# mixer.net
KiCad netlist of a schematic drawn in Altium Designer
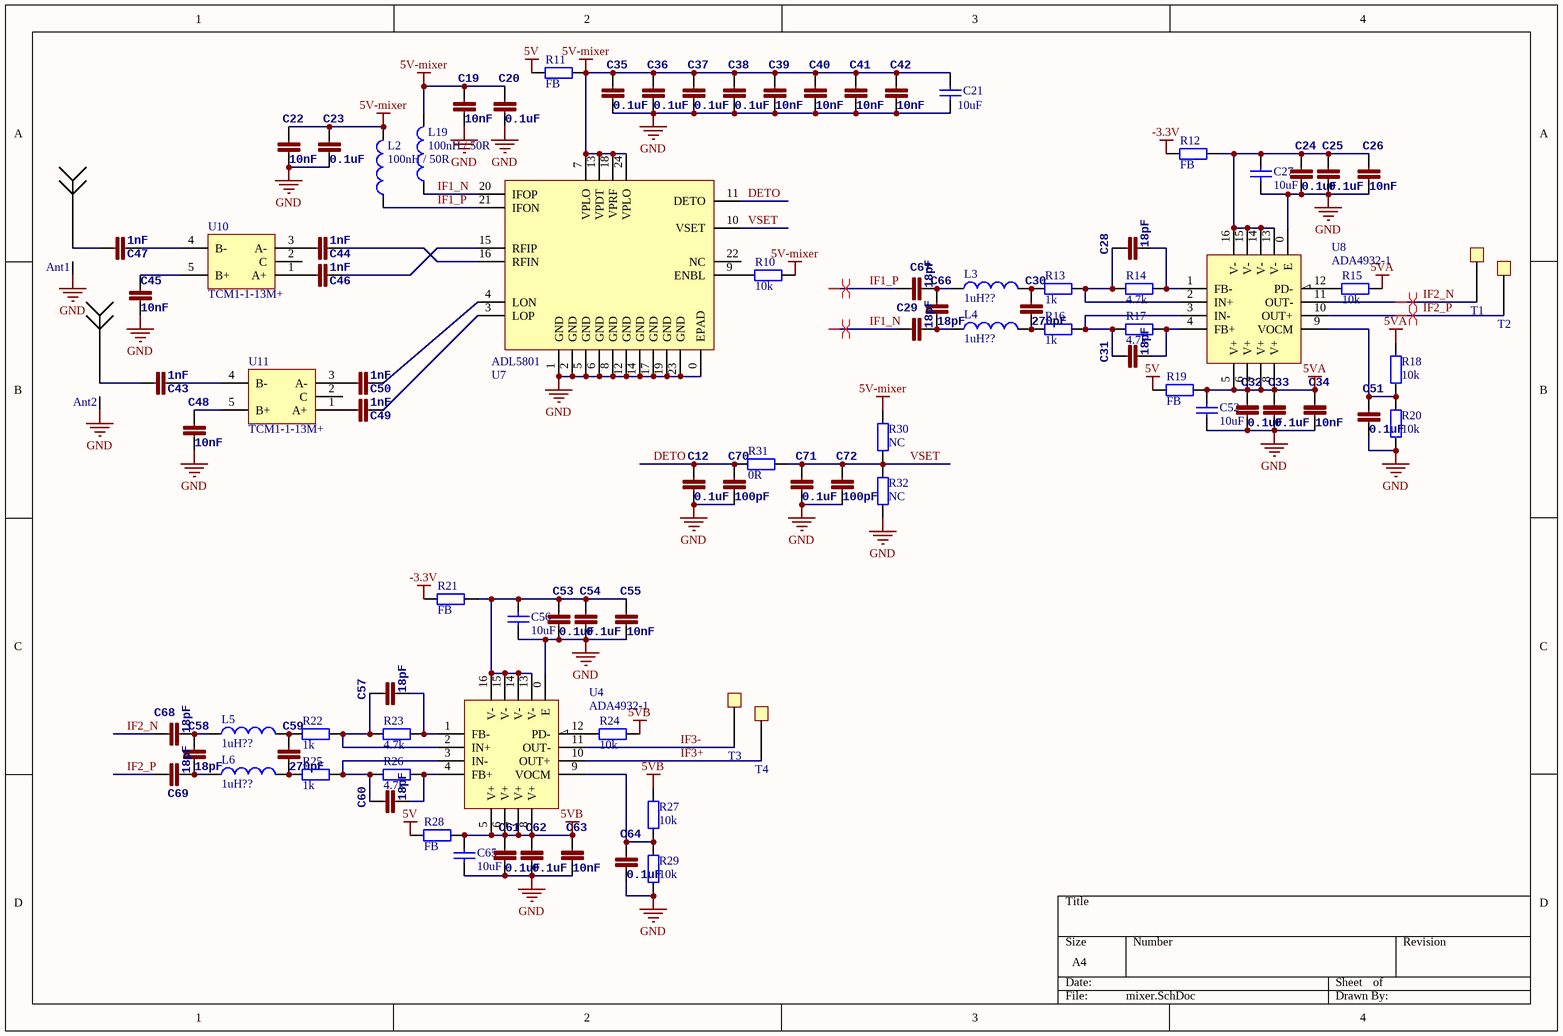
[diagram p0: mixer.SchDoc]

(export (version "E")
  (design (tool "Eeschema 10.0.6"))
  (components
    (comp (ref "Ant1") (value "Antenna") (footprint "SMA-2") (libsource (lib "F4SDR") (part "Antenna")))
    (comp (ref "Ant2") (value "Antenna") (footprint "SMA-2") (libsource (lib "F4SDR") (part "Antenna")))
    (comp (ref "C12")
      (value "0.1uF")
      (footprint "0402")
      (description "<b>Capacitor</b>\nStandard 0603 ceramic capacitor, and 0.1\" leaded capacitor.")
      (fields (field (name "PARTNO") "CC0402ZRY5V7BB104"))
      (libsource (lib "") (part "CAP0402-CAP_1"))
    )
    (comp (ref "C19")
      (value "10nF")
      (footprint "0402")
      (description "<b>Capacitor</b>\nStandard 0603 ceramic capacitor, and 0.1\" leaded capacitor.")
      (fields (field (name "PARTNO") "CC0402ZRY5V7BB104"))
      (libsource (lib "") (part "CAP0402-CAP_1"))
    )
    (comp (ref "C20")
      (value "0.1uF")
      (footprint "0402")
      (description "<b>Capacitor</b>\nStandard 0603 ceramic capacitor, and 0.1\" leaded capacitor.")
      (fields (field (name "PARTNO") "CC0402ZRY5V7BB104"))
      (libsource (lib "") (part "CAP0402-CAP_1"))
    )
    (comp (ref "C21")
      (value "10uF")
      (footprint "0805")
      (description "Capacitor")
      (fields (field (name "PUBLISHER") "Altium Limited"))
      (libsource (lib "RTC6705") (part "Cap"))
    )
    (comp (ref "C22")
      (value "10nF")
      (footprint "0402")
      (description "<b>Capacitor</b>\nStandard 0603 ceramic capacitor, and 0.1\" leaded capacitor.")
      (fields (field (name "PARTNO") "CC0402ZRY5V7BB104"))
      (libsource (lib "") (part "CAP0402-CAP_1"))
    )
    (comp (ref "C23")
      (value "0.1uF")
      (footprint "0402")
      (description "<b>Capacitor</b>\nStandard 0603 ceramic capacitor, and 0.1\" leaded capacitor.")
      (fields (field (name "PARTNO") "CC0402ZRY5V7BB104"))
      (libsource (lib "") (part "CAP0402-CAP_1"))
    )
    (comp (ref "C24")
      (value "0.1uF")
      (footprint "0402")
      (description "<b>Capacitor</b>\nStandard 0603 ceramic capacitor, and 0.1\" leaded capacitor.")
      (fields (field (name "PARTNO") "CC0402ZRY5V7BB104"))
      (libsource (lib "") (part "CAP0402-CAP_1"))
    )
    (comp (ref "C25")
      (value "0.1uF")
      (footprint "0402")
      (description "<b>Capacitor</b>\nStandard 0603 ceramic capacitor, and 0.1\" leaded capacitor.")
      (fields (field (name "PARTNO") "CC0402ZRY5V7BB104"))
      (libsource (lib "") (part "CAP0402-CAP_1"))
    )
    (comp (ref "C26")
      (value "10nF")
      (footprint "0402")
      (description "<b>Capacitor</b>\nStandard 0603 ceramic capacitor, and 0.1\" leaded capacitor.")
      (fields (field (name "PARTNO") "CC0402ZRY5V7BB104"))
      (libsource (lib "") (part "CAP0402-CAP_1"))
    )
    (comp (ref "C27")
      (value "10uF")
      (footprint "0805")
      (description "Capacitor")
      (fields (field (name "PUBLISHER") "Altium Limited"))
      (libsource (lib "RTC6705") (part "Cap"))
    )
    (comp (ref "C28")
      (value "18pF")
      (footprint "0402")
      (description "<b>Capacitor</b>\nStandard 0603 ceramic capacitor, and 0.1\" leaded capacitor.")
      (fields (field (name "PARTNO") "CC0402ZRY5V7BB104"))
      (libsource (lib "") (part "CAP0402-CAP_2"))
    )
    (comp (ref "C29")
      (value "18pF")
      (footprint "0402")
      (description "<b>Capacitor</b>\nStandard 0603 ceramic capacitor, and 0.1\" leaded capacitor.")
      (fields (field (name "PARTNO") "CC0402ZRY5V7BB104"))
      (libsource (lib "") (part "CAP0402-CAP_2"))
    )
    (comp (ref "C30")
      (value "270pF")
      (footprint "0402")
      (description "<b>Capacitor</b>\nStandard 0603 ceramic capacitor, and 0.1\" leaded capacitor.")
      (fields (field (name "PARTNO") "CC0402ZRY5V7BB104"))
      (libsource (lib "") (part "CAP0402-CAP_1"))
    )
    (comp (ref "C31")
      (value "18pF")
      (footprint "0402")
      (description "<b>Capacitor</b>\nStandard 0603 ceramic capacitor, and 0.1\" leaded capacitor.")
      (fields (field (name "PARTNO") "CC0402ZRY5V7BB104"))
      (libsource (lib "") (part "CAP0402-CAP_2"))
    )
    (comp (ref "C32")
      (value "0.1uF")
      (footprint "0402")
      (description "<b>Capacitor</b>\nStandard 0603 ceramic capacitor, and 0.1\" leaded capacitor.")
      (fields (field (name "PARTNO") "CC0402ZRY5V7BB104"))
      (libsource (lib "") (part "CAP0402-CAP_1"))
    )
    (comp (ref "C33")
      (value "0.1uF")
      (footprint "0402")
      (description "<b>Capacitor</b>\nStandard 0603 ceramic capacitor, and 0.1\" leaded capacitor.")
      (fields (field (name "PARTNO") "CC0402ZRY5V7BB104"))
      (libsource (lib "") (part "CAP0402-CAP_1"))
    )
    (comp (ref "C34")
      (value "10nF")
      (footprint "0402")
      (description "<b>Capacitor</b>\nStandard 0603 ceramic capacitor, and 0.1\" leaded capacitor.")
      (fields (field (name "PARTNO") "CC0402ZRY5V7BB104"))
      (libsource (lib "") (part "CAP0402-CAP_1"))
    )
    (comp (ref "C35")
      (value "0.1uF")
      (footprint "0402")
      (description "<b>Capacitor</b>\nStandard 0603 ceramic capacitor, and 0.1\" leaded capacitor.")
      (fields (field (name "PARTNO") "CC0402ZRY5V7BB104"))
      (libsource (lib "") (part "CAP0402-CAP_1"))
    )
    (comp (ref "C36")
      (value "0.1uF")
      (footprint "0402")
      (description "<b>Capacitor</b>\nStandard 0603 ceramic capacitor, and 0.1\" leaded capacitor.")
      (fields (field (name "PARTNO") "CC0402ZRY5V7BB104"))
      (libsource (lib "") (part "CAP0402-CAP_1"))
    )
    (comp (ref "C37")
      (value "0.1uF")
      (footprint "0402")
      (description "<b>Capacitor</b>\nStandard 0603 ceramic capacitor, and 0.1\" leaded capacitor.")
      (fields (field (name "PARTNO") "CC0402ZRY5V7BB104"))
      (libsource (lib "") (part "CAP0402-CAP_1"))
    )
    (comp (ref "C38")
      (value "0.1uF")
      (footprint "0402")
      (description "<b>Capacitor</b>\nStandard 0603 ceramic capacitor, and 0.1\" leaded capacitor.")
      (fields (field (name "PARTNO") "CC0402ZRY5V7BB104"))
      (libsource (lib "") (part "CAP0402-CAP_1"))
    )
    (comp (ref "C39")
      (value "10nF")
      (footprint "0402")
      (description "<b>Capacitor</b>\nStandard 0603 ceramic capacitor, and 0.1\" leaded capacitor.")
      (fields (field (name "PARTNO") "CC0402ZRY5V7BB104"))
      (libsource (lib "") (part "CAP0402-CAP_1"))
    )
    (comp (ref "C40")
      (value "10nF")
      (footprint "0402")
      (description "<b>Capacitor</b>\nStandard 0603 ceramic capacitor, and 0.1\" leaded capacitor.")
      (fields (field (name "PARTNO") "CC0402ZRY5V7BB104"))
      (libsource (lib "") (part "CAP0402-CAP_1"))
    )
    (comp (ref "C41")
      (value "10nF")
      (footprint "0402")
      (description "<b>Capacitor</b>\nStandard 0603 ceramic capacitor, and 0.1\" leaded capacitor.")
      (fields (field (name "PARTNO") "CC0402ZRY5V7BB104"))
      (libsource (lib "") (part "CAP0402-CAP_1"))
    )
    (comp (ref "C42")
      (value "10nF")
      (footprint "0402")
      (description "<b>Capacitor</b>\nStandard 0603 ceramic capacitor, and 0.1\" leaded capacitor.")
      (fields (field (name "PARTNO") "CC0402ZRY5V7BB104"))
      (libsource (lib "") (part "CAP0402-CAP_1"))
    )
    (comp (ref "C43")
      (value "1nF")
      (footprint "0402")
      (description "<b>Capacitor</b>\nStandard 0603 ceramic capacitor, and 0.1\" leaded capacitor.")
      (fields (field (name "PARTNO") "CC0402ZRY5V7BB104"))
      (libsource (lib "*") (part "CAP0402-CAP"))
    )
    (comp (ref "C44")
      (value "1nF")
      (footprint "0402")
      (description "<b>Capacitor</b>\nStandard 0603 ceramic capacitor, and 0.1\" leaded capacitor.")
      (fields (field (name "PARTNO") "CC0402ZRY5V7BB104"))
      (libsource (lib "*") (part "CAP0402-CAP"))
    )
    (comp (ref "C45")
      (value "10nF")
      (footprint "0402")
      (description "<b>Capacitor</b>\nStandard 0603 ceramic capacitor, and 0.1\" leaded capacitor.")
      (fields (field (name "PARTNO") "CC0402ZRY5V7BB104"))
      (libsource (lib "") (part "CAP0402-CAP_1"))
    )
    (comp (ref "C46")
      (value "1nF")
      (footprint "0402")
      (description "<b>Capacitor</b>\nStandard 0603 ceramic capacitor, and 0.1\" leaded capacitor.")
      (fields (field (name "PARTNO") "CC0402ZRY5V7BB104"))
      (libsource (lib "*") (part "CAP0402-CAP"))
    )
    (comp (ref "C47")
      (value "1nF")
      (footprint "0402")
      (description "<b>Capacitor</b>\nStandard 0603 ceramic capacitor, and 0.1\" leaded capacitor.")
      (fields (field (name "PARTNO") "CC0402ZRY5V7BB104"))
      (libsource (lib "*") (part "CAP0402-CAP"))
    )
    (comp (ref "C48")
      (value "10nF")
      (footprint "0402")
      (description "<b>Capacitor</b>\nStandard 0603 ceramic capacitor, and 0.1\" leaded capacitor.")
      (fields (field (name "PARTNO") "CC0402ZRY5V7BB104"))
      (libsource (lib "") (part "CAP0402-CAP_1"))
    )
    (comp (ref "C49")
      (value "1nF")
      (footprint "0402")
      (description "<b>Capacitor</b>\nStandard 0603 ceramic capacitor, and 0.1\" leaded capacitor.")
      (fields (field (name "PARTNO") "CC0402ZRY5V7BB104"))
      (libsource (lib "*") (part "CAP0402-CAP"))
    )
    (comp (ref "C50")
      (value "1nF")
      (footprint "0402")
      (description "<b>Capacitor</b>\nStandard 0603 ceramic capacitor, and 0.1\" leaded capacitor.")
      (fields (field (name "PARTNO") "CC0402ZRY5V7BB104"))
      (libsource (lib "*") (part "CAP0402-CAP"))
    )
    (comp (ref "C51")
      (value "0.1uF")
      (footprint "0402")
      (description "<b>Capacitor</b>\nStandard 0603 ceramic capacitor, and 0.1\" leaded capacitor.")
      (fields (field (name "PARTNO") "CC0402ZRY5V7BB104"))
      (libsource (lib "") (part "CAP0402-CAP_1"))
    )
    (comp (ref "C52")
      (value "10uF")
      (footprint "0805")
      (description "Capacitor")
      (fields (field (name "PUBLISHER") "Altium Limited"))
      (libsource (lib "RTC6705") (part "Cap"))
    )
    (comp (ref "C53")
      (value "0.1uF")
      (footprint "0402")
      (description "<b>Capacitor</b>\nStandard 0603 ceramic capacitor, and 0.1\" leaded capacitor.")
      (fields (field (name "PARTNO") "CC0402ZRY5V7BB104"))
      (libsource (lib "") (part "CAP0402-CAP_1"))
    )
    (comp (ref "C54")
      (value "0.1uF")
      (footprint "0402")
      (description "<b>Capacitor</b>\nStandard 0603 ceramic capacitor, and 0.1\" leaded capacitor.")
      (fields (field (name "PARTNO") "CC0402ZRY5V7BB104"))
      (libsource (lib "") (part "CAP0402-CAP_1"))
    )
    (comp (ref "C55")
      (value "10nF")
      (footprint "0402")
      (description "<b>Capacitor</b>\nStandard 0603 ceramic capacitor, and 0.1\" leaded capacitor.")
      (fields (field (name "PARTNO") "CC0402ZRY5V7BB104"))
      (libsource (lib "") (part "CAP0402-CAP_1"))
    )
    (comp (ref "C56")
      (value "10uF")
      (footprint "0805")
      (description "Capacitor")
      (fields (field (name "PUBLISHER") "Altium Limited"))
      (libsource (lib "RTC6705") (part "Cap"))
    )
    (comp (ref "C57")
      (value "18pF")
      (footprint "0402")
      (description "<b>Capacitor</b>\nStandard 0603 ceramic capacitor, and 0.1\" leaded capacitor.")
      (fields (field (name "PARTNO") "CC0402ZRY5V7BB104"))
      (libsource (lib "") (part "CAP0402-CAP_2"))
    )
    (comp (ref "C58")
      (value "18pF")
      (footprint "0402")
      (description "<b>Capacitor</b>\nStandard 0603 ceramic capacitor, and 0.1\" leaded capacitor.")
      (fields (field (name "PARTNO") "CC0402ZRY5V7BB104"))
      (libsource (lib "") (part "CAP0402-CAP_1"))
    )
    (comp (ref "C59")
      (value "270pF")
      (footprint "0402")
      (description "<b>Capacitor</b>\nStandard 0603 ceramic capacitor, and 0.1\" leaded capacitor.")
      (fields (field (name "PARTNO") "CC0402ZRY5V7BB104"))
      (libsource (lib "") (part "CAP0402-CAP_1"))
    )
    (comp (ref "C60")
      (value "18pF")
      (footprint "0402")
      (description "<b>Capacitor</b>\nStandard 0603 ceramic capacitor, and 0.1\" leaded capacitor.")
      (fields (field (name "PARTNO") "CC0402ZRY5V7BB104"))
      (libsource (lib "") (part "CAP0402-CAP_2"))
    )
    (comp (ref "C61")
      (value "0.1uF")
      (footprint "0402")
      (description "<b>Capacitor</b>\nStandard 0603 ceramic capacitor, and 0.1\" leaded capacitor.")
      (fields (field (name "PARTNO") "CC0402ZRY5V7BB104"))
      (libsource (lib "") (part "CAP0402-CAP_1"))
    )
    (comp (ref "C62")
      (value "0.1uF")
      (footprint "0402")
      (description "<b>Capacitor</b>\nStandard 0603 ceramic capacitor, and 0.1\" leaded capacitor.")
      (fields (field (name "PARTNO") "CC0402ZRY5V7BB104"))
      (libsource (lib "") (part "CAP0402-CAP_1"))
    )
    (comp (ref "C63")
      (value "10nF")
      (footprint "0402")
      (description "<b>Capacitor</b>\nStandard 0603 ceramic capacitor, and 0.1\" leaded capacitor.")
      (fields (field (name "PARTNO") "CC0402ZRY5V7BB104"))
      (libsource (lib "") (part "CAP0402-CAP_1"))
    )
    (comp (ref "C64")
      (value "0.1uF")
      (footprint "0402")
      (description "<b>Capacitor</b>\nStandard 0603 ceramic capacitor, and 0.1\" leaded capacitor.")
      (fields (field (name "PARTNO") "CC0402ZRY5V7BB104"))
      (libsource (lib "") (part "CAP0402-CAP_1"))
    )
    (comp (ref "C65")
      (value "10uF")
      (footprint "0805")
      (description "Capacitor")
      (fields (field (name "PUBLISHER") "Altium Limited"))
      (libsource (lib "RTC6705") (part "Cap"))
    )
    (comp (ref "C66")
      (value "18pF")
      (footprint "0402")
      (description "<b>Capacitor</b>\nStandard 0603 ceramic capacitor, and 0.1\" leaded capacitor.")
      (fields (field (name "PARTNO") "CC0402ZRY5V7BB104"))
      (libsource (lib "") (part "CAP0402-CAP_1"))
    )
    (comp (ref "C67")
      (value "18pF")
      (footprint "0402")
      (description "<b>Capacitor</b>\nStandard 0603 ceramic capacitor, and 0.1\" leaded capacitor.")
      (fields (field (name "PARTNO") "CC0402ZRY5V7BB104"))
      (libsource (lib "") (part "CAP0402-CAP_2"))
    )
    (comp (ref "C68")
      (value "18pF")
      (footprint "0402")
      (description "<b>Capacitor</b>\nStandard 0603 ceramic capacitor, and 0.1\" leaded capacitor.")
      (fields (field (name "PARTNO") "CC0402ZRY5V7BB104"))
      (libsource (lib "") (part "CAP0402-CAP_2"))
    )
    (comp (ref "C69")
      (value "18pF")
      (footprint "0402")
      (description "<b>Capacitor</b>\nStandard 0603 ceramic capacitor, and 0.1\" leaded capacitor.")
      (fields (field (name "PARTNO") "CC0402ZRY5V7BB104"))
      (libsource (lib "") (part "CAP0402-CAP_2"))
    )
    (comp (ref "C70")
      (value "100pF")
      (footprint "0402")
      (description "<b>Capacitor</b>\nStandard 0603 ceramic capacitor, and 0.1\" leaded capacitor.")
      (fields (field (name "PARTNO") "CC0402ZRY5V7BB104"))
      (libsource (lib "") (part "CAP0402-CAP_1"))
    )
    (comp (ref "C71")
      (value "0.1uF")
      (footprint "0402")
      (description "<b>Capacitor</b>\nStandard 0603 ceramic capacitor, and 0.1\" leaded capacitor.")
      (fields (field (name "PARTNO") "CC0402ZRY5V7BB104"))
      (libsource (lib "") (part "CAP0402-CAP_1"))
    )
    (comp (ref "C72")
      (value "100pF")
      (footprint "0402")
      (description "<b>Capacitor</b>\nStandard 0603 ceramic capacitor, and 0.1\" leaded capacitor.")
      (fields (field (name "PARTNO") "CC0402ZRY5V7BB104"))
      (libsource (lib "") (part "CAP0402-CAP_1"))
    )
    (comp (ref "L2")
      (value "100nH / 50R")
      (footprint "0603")
      (description "Inductor")
      (fields (field (name "PUBLISHER") "Altium Limited"))
      (libsource (lib "Miscellaneous Devices") (part "Inductor"))
    )
    (comp (ref "L3")
      (value "1uH??")
      (footprint "0805")
      (description "Inductor")
      (fields (field (name "PUBLISHER") "Altium Limited"))
      (libsource (lib "Miscellaneous Devices") (part "Inductor"))
    )
    (comp (ref "L4")
      (value "1uH??")
      (footprint "0805")
      (description "Inductor")
      (fields (field (name "PUBLISHER") "Altium Limited"))
      (libsource (lib "Miscellaneous Devices") (part "Inductor"))
    )
    (comp (ref "L5")
      (value "1uH??")
      (footprint "0805")
      (description "Inductor")
      (fields (field (name "PUBLISHER") "Altium Limited"))
      (libsource (lib "Miscellaneous Devices") (part "Inductor"))
    )
    (comp (ref "L6")
      (value "1uH??")
      (footprint "0805")
      (description "Inductor")
      (fields (field (name "PUBLISHER") "Altium Limited"))
      (libsource (lib "Miscellaneous Devices") (part "Inductor"))
    )
    (comp (ref "L19")
      (value "100nH / 50R")
      (footprint "0603")
      (description "Inductor")
      (fields (field (name "PUBLISHER") "Altium Limited"))
      (libsource (lib "Miscellaneous Devices") (part "Inductor"))
    )
    (comp (ref "R10")
      (value "10k")
      (footprint "0402")
      (description "Resistor")
      (fields (field (name "Comment") "Res2") (field (name "PUBLISHER") "Altium Limited"))
      (libsource (lib "RTC6705") (part "Res2"))
    )
    (comp (ref "R11")
      (value "FB")
      (footprint "0603")
      (description "Resistor")
      (fields (field (name "PUBLISHER") "Altium Limited"))
      (libsource (lib "Miscellaneous Devices") (part "Res2"))
    )
    (comp (ref "R12")
      (value "FB")
      (footprint "0603")
      (description "Resistor")
      (fields (field (name "PUBLISHER") "Altium Limited"))
      (libsource (lib "Miscellaneous Devices") (part "Res2"))
    )
    (comp (ref "R13")
      (value "1k")
      (footprint "0402")
      (description "Resistor")
      (fields (field (name "Comment") "Res2") (field (name "PUBLISHER") "Altium Limited"))
      (libsource (lib "RTC6705") (part "Res2"))
    )
    (comp (ref "R14")
      (value "4.7k")
      (footprint "0402")
      (description "Resistor")
      (fields (field (name "Comment") "Res2") (field (name "PUBLISHER") "Altium Limited"))
      (libsource (lib "RTC6705") (part "Res2"))
    )
    (comp (ref "R15")
      (value "10k")
      (footprint "0402")
      (description "Resistor")
      (fields (field (name "Comment") "Res2") (field (name "PUBLISHER") "Altium Limited"))
      (libsource (lib "RTC6705") (part "Res2"))
    )
    (comp (ref "R16")
      (value "1k")
      (footprint "0402")
      (description "Resistor")
      (fields (field (name "Comment") "Res2") (field (name "PUBLISHER") "Altium Limited"))
      (libsource (lib "RTC6705") (part "Res2"))
    )
    (comp (ref "R17")
      (value "4.7k")
      (footprint "0402")
      (description "Resistor")
      (fields (field (name "Comment") "Res2") (field (name "PUBLISHER") "Altium Limited"))
      (libsource (lib "RTC6705") (part "Res2"))
    )
    (comp (ref "R18")
      (value "10k")
      (footprint "0402")
      (description "Resistor")
      (fields (field (name "Comment") "Res2") (field (name "PUBLISHER") "Altium Limited"))
      (libsource (lib "") (part "Res2_1"))
    )
    (comp (ref "R19")
      (value "FB")
      (footprint "0603")
      (description "Resistor")
      (fields (field (name "PUBLISHER") "Altium Limited"))
      (libsource (lib "Miscellaneous Devices") (part "Res2"))
    )
    (comp (ref "R20")
      (value "10k")
      (footprint "0402")
      (description "Resistor")
      (fields (field (name "Comment") "Res2") (field (name "PUBLISHER") "Altium Limited"))
      (libsource (lib "") (part "Res2_1"))
    )
    (comp (ref "R21")
      (value "FB")
      (footprint "0603")
      (description "Resistor")
      (fields (field (name "PUBLISHER") "Altium Limited"))
      (libsource (lib "Miscellaneous Devices") (part "Res2"))
    )
    (comp (ref "R22")
      (value "1k")
      (footprint "0402")
      (description "Resistor")
      (fields (field (name "Comment") "Res2") (field (name "PUBLISHER") "Altium Limited"))
      (libsource (lib "RTC6705") (part "Res2"))
    )
    (comp (ref "R23")
      (value "4.7k")
      (footprint "0402")
      (description "Resistor")
      (fields (field (name "Comment") "Res2") (field (name "PUBLISHER") "Altium Limited"))
      (libsource (lib "RTC6705") (part "Res2"))
    )
    (comp (ref "R24")
      (value "10k")
      (footprint "0402")
      (description "Resistor")
      (fields (field (name "Comment") "Res2") (field (name "PUBLISHER") "Altium Limited"))
      (libsource (lib "RTC6705") (part "Res2"))
    )
    (comp (ref "R25")
      (value "1k")
      (footprint "0402")
      (description "Resistor")
      (fields (field (name "Comment") "Res2") (field (name "PUBLISHER") "Altium Limited"))
      (libsource (lib "RTC6705") (part "Res2"))
    )
    (comp (ref "R26")
      (value "4.7k")
      (footprint "0402")
      (description "Resistor")
      (fields (field (name "Comment") "Res2") (field (name "PUBLISHER") "Altium Limited"))
      (libsource (lib "RTC6705") (part "Res2"))
    )
    (comp (ref "R27")
      (value "10k")
      (footprint "0402")
      (description "Resistor")
      (fields (field (name "Comment") "Res2") (field (name "PUBLISHER") "Altium Limited"))
      (libsource (lib "") (part "Res2_1"))
    )
    (comp (ref "R28")
      (value "FB")
      (footprint "0603")
      (description "Resistor")
      (fields (field (name "PUBLISHER") "Altium Limited"))
      (libsource (lib "Miscellaneous Devices") (part "Res2"))
    )
    (comp (ref "R29")
      (value "10k")
      (footprint "0402")
      (description "Resistor")
      (fields (field (name "Comment") "Res2") (field (name "PUBLISHER") "Altium Limited"))
      (libsource (lib "") (part "Res2_1"))
    )
    (comp (ref "R30")
      (value "NC")
      (footprint "0402")
      (description "Resistor")
      (fields (field (name "Comment") "Res2") (field (name "PUBLISHER") "Altium Limited"))
      (libsource (lib "") (part "Res2_1"))
    )
    (comp (ref "R31")
      (value "0R")
      (footprint "0402")
      (description "Resistor")
      (fields (field (name "Comment") "Res2") (field (name "PUBLISHER") "Altium Limited"))
      (libsource (lib "RTC6705") (part "Res2"))
    )
    (comp (ref "R32")
      (value "NC")
      (footprint "0402")
      (description "Resistor")
      (fields (field (name "Comment") "Res2") (field (name "PUBLISHER") "Altium Limited"))
      (libsource (lib "") (part "Res2_1"))
    )
    (comp (ref "T1") (value "TestPad") (footprint "TestPad - 1mm") (libsource (lib "sch") (part "TestPad")))
    (comp (ref "T2") (value "TestPad") (footprint "TestPad - 1mm") (libsource (lib "sch") (part "TestPad")))
    (comp (ref "T3") (value "TestPad") (footprint "TestPad - 1mm") (libsource (lib "sch") (part "TestPad")))
    (comp (ref "T4") (value "TestPad") (footprint "TestPad - 1mm") (libsource (lib "sch") (part "TestPad")))
    (comp (ref "U4") (value "ADA4932-1") (footprint "ADA4932-1") (libsource (lib "F4SDR") (part "ADA4932-1")))
    (comp (ref "U7") (value "ADL5801") (footprint "ADL5801") (libsource (lib "F4SDR") (part "ADL5801")))
    (comp (ref "U8") (value "ADA4932-1") (footprint "ADA4932-1") (libsource (lib "F4SDR") (part "ADA4932-1")))
    (comp (ref "U10")
      (value "TCM1-1-13M+")
      (footprint "TCM-63AX+")
      (libsource (lib "F4SDR") (part "TCM1-1-13M+"))
    )
    (comp (ref "U11")
      (value "TCM1-1-13M+")
      (footprint "TCM-63AX+")
      (libsource (lib "F4SDR") (part "TCM1-1-13M+"))
    )
  )
  (nets
    (net (code "1") (name "-3.3V") (class "Default")
      (node (ref "R12") (pin "1") (pinfunction "1_1") (pintype "passive"))
      (node (ref "R21") (pin "1") (pinfunction "1_1") (pintype "passive"))
    )
    (net (code "2") (name "/DETO") (class "Default")
      (node (ref "C12") (pin "2") (pinfunction "2_2") (pintype "passive"))
      (node (ref "C70") (pin "2") (pinfunction "2_2") (pintype "passive"))
      (node (ref "R31") (pin "1") (pinfunction "1_1") (pintype "passive"))
      (node (ref "U7") (pin "11") (pinfunction "DETO_11") (pintype "passive"))
    )
    (net (code "3") (name "/IF1_N") (class "Default")
      (node (ref "C29") (pin "2") (pinfunction "2_2") (pintype "passive"))
      (node (ref "L19") (pin "1") (pinfunction "1_1") (pintype "passive"))
      (node (ref "U7") (pin "20") (pinfunction "IFOP_20") (pintype "passive"))
    )
    (net (code "4") (name "/IF1_P") (class "Default")
      (node (ref "C67") (pin "2") (pinfunction "2_2") (pintype "passive"))
      (node (ref "L2") (pin "1") (pinfunction "1_1") (pintype "passive"))
      (node (ref "U7") (pin "21") (pinfunction "IFON_21") (pintype "passive"))
    )
    (net (code "5") (name "/IF2_N") (class "Default")
      (node (ref "C68") (pin "2") (pinfunction "2_2") (pintype "passive"))
      (node (ref "T1") (pin "1") (pinfunction "3_1") (pintype "passive"))
      (node (ref "U8") (pin "11") (pinfunction "OUT-_11") (pintype "passive"))
    )
    (net (code "6") (name "/IF2_P") (class "Default")
      (node (ref "C69") (pin "2") (pinfunction "2_2") (pintype "passive"))
      (node (ref "T2") (pin "1") (pinfunction "3_1") (pintype "passive"))
      (node (ref "U8") (pin "10") (pinfunction "OUT+_10") (pintype "passive"))
    )
    (net (code "7") (name "/IF3+") (class "Default")
      (node (ref "T4") (pin "1") (pinfunction "3_1") (pintype "passive"))
      (node (ref "U4") (pin "10") (pinfunction "OUT+_10") (pintype "passive"))
    )
    (net (code "8") (name "/IF3-") (class "Default")
      (node (ref "T3") (pin "1") (pinfunction "3_1") (pintype "passive"))
      (node (ref "U4") (pin "11") (pinfunction "OUT-_11") (pintype "passive"))
    )
    (net (code "9") (name "/VSET") (class "Default")
      (node (ref "C71") (pin "2") (pinfunction "2_2") (pintype "passive"))
      (node (ref "C72") (pin "2") (pinfunction "2_2") (pintype "passive"))
      (node (ref "R30") (pin "1") (pinfunction "1_1") (pintype "passive"))
      (node (ref "R31") (pin "2") (pinfunction "2_2") (pintype "passive"))
      (node (ref "R32") (pin "2") (pinfunction "2_2") (pintype "passive"))
      (node (ref "U7") (pin "10") (pinfunction "VSET_10") (pintype "passive"))
    )
    (net (code "10") (name "5V") (class "Default")
      (node (ref "R11") (pin "1") (pinfunction "1_1") (pintype "passive"))
      (node (ref "R19") (pin "1") (pinfunction "1_1") (pintype "passive"))
      (node (ref "R28") (pin "1") (pinfunction "1_1") (pintype "passive"))
    )
    (net (code "11") (name "5V-mixer") (class "Default")
      (node (ref "C19") (pin "2") (pinfunction "2_2") (pintype "passive"))
      (node (ref "C20") (pin "2") (pinfunction "2_2") (pintype "passive"))
      (node (ref "C21") (pin "2") (pinfunction "2_2") (pintype "passive"))
      (node (ref "C22") (pin "2") (pinfunction "2_2") (pintype "passive"))
      (node (ref "C23") (pin "2") (pinfunction "2_2") (pintype "passive"))
      (node (ref "C35") (pin "2") (pinfunction "2_2") (pintype "passive"))
      (node (ref "C36") (pin "2") (pinfunction "2_2") (pintype "passive"))
      (node (ref "C37") (pin "2") (pinfunction "2_2") (pintype "passive"))
      (node (ref "C38") (pin "2") (pinfunction "2_2") (pintype "passive"))
      (node (ref "C39") (pin "2") (pinfunction "2_2") (pintype "passive"))
      (node (ref "C40") (pin "2") (pinfunction "2_2") (pintype "passive"))
      (node (ref "C41") (pin "2") (pinfunction "2_2") (pintype "passive"))
      (node (ref "C42") (pin "2") (pinfunction "2_2") (pintype "passive"))
      (node (ref "L19") (pin "2") (pinfunction "2_2") (pintype "passive"))
      (node (ref "L2") (pin "2") (pinfunction "2_2") (pintype "passive"))
      (node (ref "R10") (pin "2") (pinfunction "2_2") (pintype "passive"))
      (node (ref "R11") (pin "2") (pinfunction "2_2") (pintype "passive"))
      (node (ref "R30") (pin "2") (pinfunction "2_2") (pintype "passive"))
      (node (ref "U7") (pin "13") (pinfunction "VPDT_13") (pintype "passive"))
      (node (ref "U7") (pin "18") (pinfunction "VPRF_18") (pintype "passive"))
      (node (ref "U7") (pin "24") (pinfunction "VPLO_24") (pintype "passive"))
      (node (ref "U7") (pin "7") (pinfunction "VPLO_7") (pintype "passive"))
    )
    (net (code "12") (name "5VA") (class "Default")
      (node (ref "C32") (pin "2") (pinfunction "2_2") (pintype "passive"))
      (node (ref "C33") (pin "2") (pinfunction "2_2") (pintype "passive"))
      (node (ref "C34") (pin "2") (pinfunction "2_2") (pintype "passive"))
      (node (ref "C52") (pin "1") (pinfunction "1_1") (pintype "passive"))
      (node (ref "R15") (pin "2") (pinfunction "2_2") (pintype "passive"))
      (node (ref "R18") (pin "2") (pinfunction "2_2") (pintype "passive"))
      (node (ref "R19") (pin "2") (pinfunction "2_2") (pintype "passive"))
      (node (ref "U8") (pin "5") (pinfunction "V+_5") (pintype "passive"))
      (node (ref "U8") (pin "6") (pinfunction "V+_6") (pintype "passive"))
      (node (ref "U8") (pin "7") (pinfunction "V+_7") (pintype "passive"))
      (node (ref "U8") (pin "8") (pinfunction "V+_8") (pintype "passive"))
    )
    (net (code "13") (name "5VB") (class "Default")
      (node (ref "C61") (pin "2") (pinfunction "2_2") (pintype "passive"))
      (node (ref "C62") (pin "2") (pinfunction "2_2") (pintype "passive"))
      (node (ref "C63") (pin "2") (pinfunction "2_2") (pintype "passive"))
      (node (ref "C65") (pin "1") (pinfunction "1_1") (pintype "passive"))
      (node (ref "R24") (pin "2") (pinfunction "2_2") (pintype "passive"))
      (node (ref "R27") (pin "2") (pinfunction "2_2") (pintype "passive"))
      (node (ref "R28") (pin "2") (pinfunction "2_2") (pintype "passive"))
      (node (ref "U4") (pin "5") (pinfunction "V+_5") (pintype "passive"))
      (node (ref "U4") (pin "6") (pinfunction "V+_6") (pintype "passive"))
      (node (ref "U4") (pin "7") (pinfunction "V+_7") (pintype "passive"))
      (node (ref "U4") (pin "8") (pinfunction "V+_8") (pintype "passive"))
    )
    (net (code "14") (name "GND") (class "Default")
      (node (ref "Ant1") (pin "GND") (pinfunction "G_GND") (pintype "passive"))
      (node (ref "Ant2") (pin "GND") (pinfunction "G_GND") (pintype "passive"))
      (node (ref "C12") (pin "1") (pinfunction "1_1") (pintype "passive"))
      (node (ref "C19") (pin "1") (pinfunction "1_1") (pintype "passive"))
      (node (ref "C20") (pin "1") (pinfunction "1_1") (pintype "passive"))
      (node (ref "C21") (pin "1") (pinfunction "1_1") (pintype "passive"))
      (node (ref "C22") (pin "1") (pinfunction "1_1") (pintype "passive"))
      (node (ref "C23") (pin "1") (pinfunction "1_1") (pintype "passive"))
      (node (ref "C24") (pin "1") (pinfunction "1_1") (pintype "passive"))
      (node (ref "C25") (pin "1") (pinfunction "1_1") (pintype "passive"))
      (node (ref "C26") (pin "1") (pinfunction "1_1") (pintype "passive"))
      (node (ref "C27") (pin "2") (pinfunction "2_2") (pintype "passive"))
      (node (ref "C32") (pin "1") (pinfunction "1_1") (pintype "passive"))
      (node (ref "C33") (pin "1") (pinfunction "1_1") (pintype "passive"))
      (node (ref "C34") (pin "1") (pinfunction "1_1") (pintype "passive"))
      (node (ref "C35") (pin "1") (pinfunction "1_1") (pintype "passive"))
      (node (ref "C36") (pin "1") (pinfunction "1_1") (pintype "passive"))
      (node (ref "C37") (pin "1") (pinfunction "1_1") (pintype "passive"))
      (node (ref "C38") (pin "1") (pinfunction "1_1") (pintype "passive"))
      (node (ref "C39") (pin "1") (pinfunction "1_1") (pintype "passive"))
      (node (ref "C40") (pin "1") (pinfunction "1_1") (pintype "passive"))
      (node (ref "C41") (pin "1") (pinfunction "1_1") (pintype "passive"))
      (node (ref "C42") (pin "1") (pinfunction "1_1") (pintype "passive"))
      (node (ref "C45") (pin "1") (pinfunction "1_1") (pintype "passive"))
      (node (ref "C48") (pin "1") (pinfunction "1_1") (pintype "passive"))
      (node (ref "C51") (pin "1") (pinfunction "1_1") (pintype "passive"))
      (node (ref "C52") (pin "2") (pinfunction "2_2") (pintype "passive"))
      (node (ref "C53") (pin "1") (pinfunction "1_1") (pintype "passive"))
      (node (ref "C54") (pin "1") (pinfunction "1_1") (pintype "passive"))
      (node (ref "C55") (pin "1") (pinfunction "1_1") (pintype "passive"))
      (node (ref "C56") (pin "2") (pinfunction "2_2") (pintype "passive"))
      (node (ref "C61") (pin "1") (pinfunction "1_1") (pintype "passive"))
      (node (ref "C62") (pin "1") (pinfunction "1_1") (pintype "passive"))
      (node (ref "C63") (pin "1") (pinfunction "1_1") (pintype "passive"))
      (node (ref "C64") (pin "1") (pinfunction "1_1") (pintype "passive"))
      (node (ref "C65") (pin "2") (pinfunction "2_2") (pintype "passive"))
      (node (ref "C70") (pin "1") (pinfunction "1_1") (pintype "passive"))
      (node (ref "C71") (pin "1") (pinfunction "1_1") (pintype "passive"))
      (node (ref "C72") (pin "1") (pinfunction "1_1") (pintype "passive"))
      (node (ref "R20") (pin "1") (pinfunction "1_1") (pintype "passive"))
      (node (ref "R29") (pin "1") (pinfunction "1_1") (pintype "passive"))
      (node (ref "R32") (pin "1") (pinfunction "1_1") (pintype "passive"))
      (node (ref "U4") (pin "0") (pinfunction "E_0") (pintype "passive"))
      (node (ref "U7") (pin "0") (pinfunction "EPAD_0") (pintype "passive"))
      (node (ref "U7") (pin "1") (pinfunction "GND_1") (pintype "passive"))
      (node (ref "U7") (pin "12") (pinfunction "GND_12") (pintype "passive"))
      (node (ref "U7") (pin "14") (pinfunction "GND_14") (pintype "passive"))
      (node (ref "U7") (pin "17") (pinfunction "GND_17") (pintype "passive"))
      (node (ref "U7") (pin "19") (pinfunction "GND_19") (pintype "passive"))
      (node (ref "U7") (pin "2") (pinfunction "GND_2") (pintype "passive"))
      (node (ref "U7") (pin "23") (pinfunction "GND_23") (pintype "passive"))
      (node (ref "U7") (pin "5") (pinfunction "GND_5") (pintype "passive"))
      (node (ref "U7") (pin "6") (pinfunction "GND_6") (pintype "passive"))
      (node (ref "U7") (pin "8") (pinfunction "GND_8") (pintype "passive"))
      (node (ref "U8") (pin "0") (pinfunction "E_0") (pintype "passive"))
    )
    (net (code "15") (name "Net-(Ant1-Pad1)") (class "Default")
      (node (ref "Ant1") (pin "1") (pinfunction "1_1") (pintype "passive"))
      (node (ref "C47") (pin "1") (pinfunction "1_1") (pintype "passive"))
    )
    (net (code "16") (name "Net-(Ant2-Pad1)") (class "Default")
      (node (ref "Ant2") (pin "1") (pinfunction "1_1") (pintype "passive"))
      (node (ref "C43") (pin "1") (pinfunction "1_1") (pintype "passive"))
    )
    (net (code "17") (name "Net-(C24-Pad2)") (class "Default")
      (node (ref "C24") (pin "2") (pinfunction "2_2") (pintype "passive"))
      (node (ref "C25") (pin "2") (pinfunction "2_2") (pintype "passive"))
      (node (ref "C26") (pin "2") (pinfunction "2_2") (pintype "passive"))
      (node (ref "C27") (pin "1") (pinfunction "1_1") (pintype "passive"))
      (node (ref "R12") (pin "2") (pinfunction "2_2") (pintype "passive"))
      (node (ref "U8") (pin "13") (pinfunction "V-_13") (pintype "passive"))
      (node (ref "U8") (pin "14") (pinfunction "V-_14") (pintype "passive"))
      (node (ref "U8") (pin "15") (pinfunction "V-_15") (pintype "passive"))
      (node (ref "U8") (pin "16") (pinfunction "V-_16") (pintype "passive"))
    )
    (net (code "18") (name "Net-(C29-Pad1)") (class "Default")
      (node (ref "C29") (pin "1") (pinfunction "1_1") (pintype "passive"))
      (node (ref "C66") (pin "1") (pinfunction "1_1") (pintype "passive"))
      (node (ref "L4") (pin "1") (pinfunction "1_1") (pintype "passive"))
    )
    (net (code "19") (name "Net-(C30-Pad1)") (class "Default")
      (node (ref "C30") (pin "1") (pinfunction "1_1") (pintype "passive"))
      (node (ref "L4") (pin "2") (pinfunction "2_2") (pintype "passive"))
      (node (ref "R16") (pin "1") (pinfunction "1_1") (pintype "passive"))
    )
    (net (code "20") (name "Net-(C30-Pad2)") (class "Default")
      (node (ref "C30") (pin "2") (pinfunction "2_2") (pintype "passive"))
      (node (ref "L3") (pin "2") (pinfunction "2_2") (pintype "passive"))
      (node (ref "R13") (pin "1") (pinfunction "1_1") (pintype "passive"))
    )
    (net (code "21") (name "Net-(C53-Pad2)") (class "Default")
      (node (ref "C53") (pin "2") (pinfunction "2_2") (pintype "passive"))
      (node (ref "C54") (pin "2") (pinfunction "2_2") (pintype "passive"))
      (node (ref "C55") (pin "2") (pinfunction "2_2") (pintype "passive"))
      (node (ref "C56") (pin "1") (pinfunction "1_1") (pintype "passive"))
      (node (ref "R21") (pin "2") (pinfunction "2_2") (pintype "passive"))
      (node (ref "U4") (pin "13") (pinfunction "V-_13") (pintype "passive"))
      (node (ref "U4") (pin "14") (pinfunction "V-_14") (pintype "passive"))
      (node (ref "U4") (pin "15") (pinfunction "V-_15") (pintype "passive"))
      (node (ref "U4") (pin "16") (pinfunction "V-_16") (pintype "passive"))
    )
    (net (code "22") (name "Net-(C58-Pad1)") (class "Default")
      (node (ref "C58") (pin "1") (pinfunction "1_1") (pintype "passive"))
      (node (ref "C69") (pin "1") (pinfunction "1_1") (pintype "passive"))
      (node (ref "L6") (pin "1") (pinfunction "1_1") (pintype "passive"))
    )
    (net (code "23") (name "Net-(C58-Pad2)") (class "Default")
      (node (ref "C58") (pin "2") (pinfunction "2_2") (pintype "passive"))
      (node (ref "C68") (pin "1") (pinfunction "1_1") (pintype "passive"))
      (node (ref "L5") (pin "1") (pinfunction "1_1") (pintype "passive"))
    )
    (net (code "24") (name "Net-(C59-Pad1)") (class "Default")
      (node (ref "C59") (pin "1") (pinfunction "1_1") (pintype "passive"))
      (node (ref "L6") (pin "2") (pinfunction "2_2") (pintype "passive"))
      (node (ref "R25") (pin "1") (pinfunction "1_1") (pintype "passive"))
    )
    (net (code "25") (name "Net-(C59-Pad2)") (class "Default")
      (node (ref "C59") (pin "2") (pinfunction "2_2") (pintype "passive"))
      (node (ref "L5") (pin "2") (pinfunction "2_2") (pintype "passive"))
      (node (ref "R22") (pin "1") (pinfunction "1_1") (pintype "passive"))
    )
    (net (code "26") (name "Net-(C66-Pad2)") (class "Default")
      (node (ref "C66") (pin "2") (pinfunction "2_2") (pintype "passive"))
      (node (ref "C67") (pin "1") (pinfunction "1_1") (pintype "passive"))
      (node (ref "L3") (pin "1") (pinfunction "1_1") (pintype "passive"))
    )
    (net (code "27") (name "Net-(U4-FB+)") (class "Default")
      (node (ref "C60") (pin "1") (pinfunction "1_1") (pintype "passive"))
      (node (ref "R26") (pin "2") (pinfunction "2_2") (pintype "passive"))
      (node (ref "U4") (pin "4") (pinfunction "FB+_4") (pintype "passive"))
    )
    (net (code "28") (name "Net-(U4-FB-)") (class "Default")
      (node (ref "C57") (pin "1") (pinfunction "1_1") (pintype "passive"))
      (node (ref "R23") (pin "2") (pinfunction "2_2") (pintype "passive"))
      (node (ref "U4") (pin "1") (pinfunction "FB-_1") (pintype "passive"))
    )
    (net (code "29") (name "Net-(U4-IN+)") (class "Default")
      (node (ref "C57") (pin "2") (pinfunction "2_2") (pintype "passive"))
      (node (ref "R22") (pin "2") (pinfunction "2_2") (pintype "passive"))
      (node (ref "R23") (pin "1") (pinfunction "1_1") (pintype "passive"))
      (node (ref "U4") (pin "2") (pinfunction "IN+_2") (pintype "passive"))
    )
    (net (code "30") (name "Net-(U4-IN-)") (class "Default")
      (node (ref "C60") (pin "2") (pinfunction "2_2") (pintype "passive"))
      (node (ref "R25") (pin "2") (pinfunction "2_2") (pintype "passive"))
      (node (ref "R26") (pin "1") (pinfunction "1_1") (pintype "passive"))
      (node (ref "U4") (pin "3") (pinfunction "IN-_3") (pintype "passive"))
    )
    (net (code "31") (name "Net-(U4-PD-)") (class "Default")
      (node (ref "R24") (pin "1") (pinfunction "1_1") (pintype "passive"))
      (node (ref "U4") (pin "12") (pinfunction "PD-_12") (pintype "passive"))
    )
    (net (code "32") (name "Net-(U4-VOCM)") (class "Default")
      (node (ref "C64") (pin "2") (pinfunction "2_2") (pintype "passive"))
      (node (ref "R27") (pin "1") (pinfunction "1_1") (pintype "passive"))
      (node (ref "R29") (pin "2") (pinfunction "2_2") (pintype "passive"))
      (node (ref "U4") (pin "9") (pinfunction "VOCM_9") (pintype "passive"))
    )
    (net (code "33") (name "Net-(U7-ENBL)") (class "Default")
      (node (ref "R10") (pin "1") (pinfunction "1_1") (pintype "passive"))
      (node (ref "U7") (pin "9") (pinfunction "ENBL_9") (pintype "passive"))
    )
    (net (code "34") (name "Net-(U7-LON)") (class "Default")
      (node (ref "C50") (pin "2") (pinfunction "2_2") (pintype "passive"))
      (node (ref "U7") (pin "4") (pinfunction "LON_4") (pintype "passive"))
    )
    (net (code "35") (name "Net-(U7-LOP)") (class "Default")
      (node (ref "C49") (pin "2") (pinfunction "2_2") (pintype "passive"))
      (node (ref "U7") (pin "3") (pinfunction "LOP_3") (pintype "passive"))
    )
    (net (code "36") (name "Net-(U7-RFIN)") (class "Default")
      (node (ref "C44") (pin "2") (pinfunction "2_2") (pintype "passive"))
      (node (ref "U7") (pin "16") (pinfunction "RFIN_16") (pintype "passive"))
    )
    (net (code "37") (name "Net-(U7-RFIP)") (class "Default")
      (node (ref "C46") (pin "2") (pinfunction "2_2") (pintype "passive"))
      (node (ref "U7") (pin "15") (pinfunction "RFIP_15") (pintype "passive"))
    )
    (net (code "38") (name "Net-(U8-FB+)") (class "Default")
      (node (ref "C31") (pin "1") (pinfunction "1_1") (pintype "passive"))
      (node (ref "R17") (pin "2") (pinfunction "2_2") (pintype "passive"))
      (node (ref "U8") (pin "4") (pinfunction "FB+_4") (pintype "passive"))
    )
    (net (code "39") (name "Net-(U8-FB-)") (class "Default")
      (node (ref "C28") (pin "1") (pinfunction "1_1") (pintype "passive"))
      (node (ref "R14") (pin "2") (pinfunction "2_2") (pintype "passive"))
      (node (ref "U8") (pin "1") (pinfunction "FB-_1") (pintype "passive"))
    )
    (net (code "40") (name "Net-(U8-IN+)") (class "Default")
      (node (ref "C28") (pin "2") (pinfunction "2_2") (pintype "passive"))
      (node (ref "R13") (pin "2") (pinfunction "2_2") (pintype "passive"))
      (node (ref "R14") (pin "1") (pinfunction "1_1") (pintype "passive"))
      (node (ref "U8") (pin "2") (pinfunction "IN+_2") (pintype "passive"))
    )
    (net (code "41") (name "Net-(U8-IN-)") (class "Default")
      (node (ref "C31") (pin "2") (pinfunction "2_2") (pintype "passive"))
      (node (ref "R16") (pin "2") (pinfunction "2_2") (pintype "passive"))
      (node (ref "R17") (pin "1") (pinfunction "1_1") (pintype "passive"))
      (node (ref "U8") (pin "3") (pinfunction "IN-_3") (pintype "passive"))
    )
    (net (code "42") (name "Net-(U8-PD-)") (class "Default")
      (node (ref "R15") (pin "1") (pinfunction "1_1") (pintype "passive"))
      (node (ref "U8") (pin "12") (pinfunction "PD-_12") (pintype "passive"))
    )
    (net (code "43") (name "Net-(U8-VOCM)") (class "Default")
      (node (ref "C51") (pin "2") (pinfunction "2_2") (pintype "passive"))
      (node (ref "R18") (pin "1") (pinfunction "1_1") (pintype "passive"))
      (node (ref "R20") (pin "2") (pinfunction "2_2") (pintype "passive"))
      (node (ref "U8") (pin "9") (pinfunction "VOCM_9") (pintype "passive"))
    )
    (net (code "44") (name "Net-(U10-A+)") (class "Default")
      (node (ref "C46") (pin "1") (pinfunction "1_1") (pintype "passive"))
      (node (ref "U10") (pin "1") (pinfunction "A+_1") (pintype "passive"))
    )
    (net (code "45") (name "Net-(U10-A-)") (class "Default")
      (node (ref "C44") (pin "1") (pinfunction "1_1") (pintype "passive"))
      (node (ref "U10") (pin "3") (pinfunction "A-_3") (pintype "passive"))
    )
    (net (code "46") (name "Net-(U10-B+)") (class "Default")
      (node (ref "C45") (pin "2") (pinfunction "2_2") (pintype "passive"))
      (node (ref "U10") (pin "5") (pinfunction "B+_5") (pintype "passive"))
    )
    (net (code "47") (name "Net-(U10-B-)") (class "Default")
      (node (ref "C47") (pin "2") (pinfunction "2_2") (pintype "passive"))
      (node (ref "U10") (pin "4") (pinfunction "B-_4") (pintype "passive"))
    )
    (net (code "48") (name "Net-(U11-A+)") (class "Default")
      (node (ref "C49") (pin "1") (pinfunction "1_1") (pintype "passive"))
      (node (ref "U11") (pin "1") (pinfunction "A+_1") (pintype "passive"))
    )
    (net (code "49") (name "Net-(U11-A-)") (class "Default")
      (node (ref "C50") (pin "1") (pinfunction "1_1") (pintype "passive"))
      (node (ref "U11") (pin "3") (pinfunction "A-_3") (pintype "passive"))
    )
    (net (code "50") (name "Net-(U11-B+)") (class "Default")
      (node (ref "C48") (pin "2") (pinfunction "2_2") (pintype "passive"))
      (node (ref "U11") (pin "5") (pinfunction "B+_5") (pintype "passive"))
    )
    (net (code "51") (name "Net-(U11-B-)") (class "Default")
      (node (ref "C43") (pin "2") (pinfunction "2_2") (pintype "passive"))
      (node (ref "U11") (pin "4") (pinfunction "B-_4") (pintype "passive"))
    )
    (net (code "52") (name "unconnected-(U7-NC-Pad22)") (class "Default")
      (node (ref "U7") (pin "22") (pinfunction "NC_22") (pintype "passive"))
    )
    (net (code "53") (name "unconnected-(U10-C-Pad2)") (class "Default")
      (node (ref "U10") (pin "2") (pinfunction "C_2") (pintype "passive"))
    )
    (net (code "54") (name "unconnected-(U11-C-Pad2)") (class "Default")
      (node (ref "U11") (pin "2") (pinfunction "C_2") (pintype "passive"))
    )
  )
)
